# ECU_AutoRC_UC1_r00.net
KiCad netlist of a schematic drawn in Altium Designer
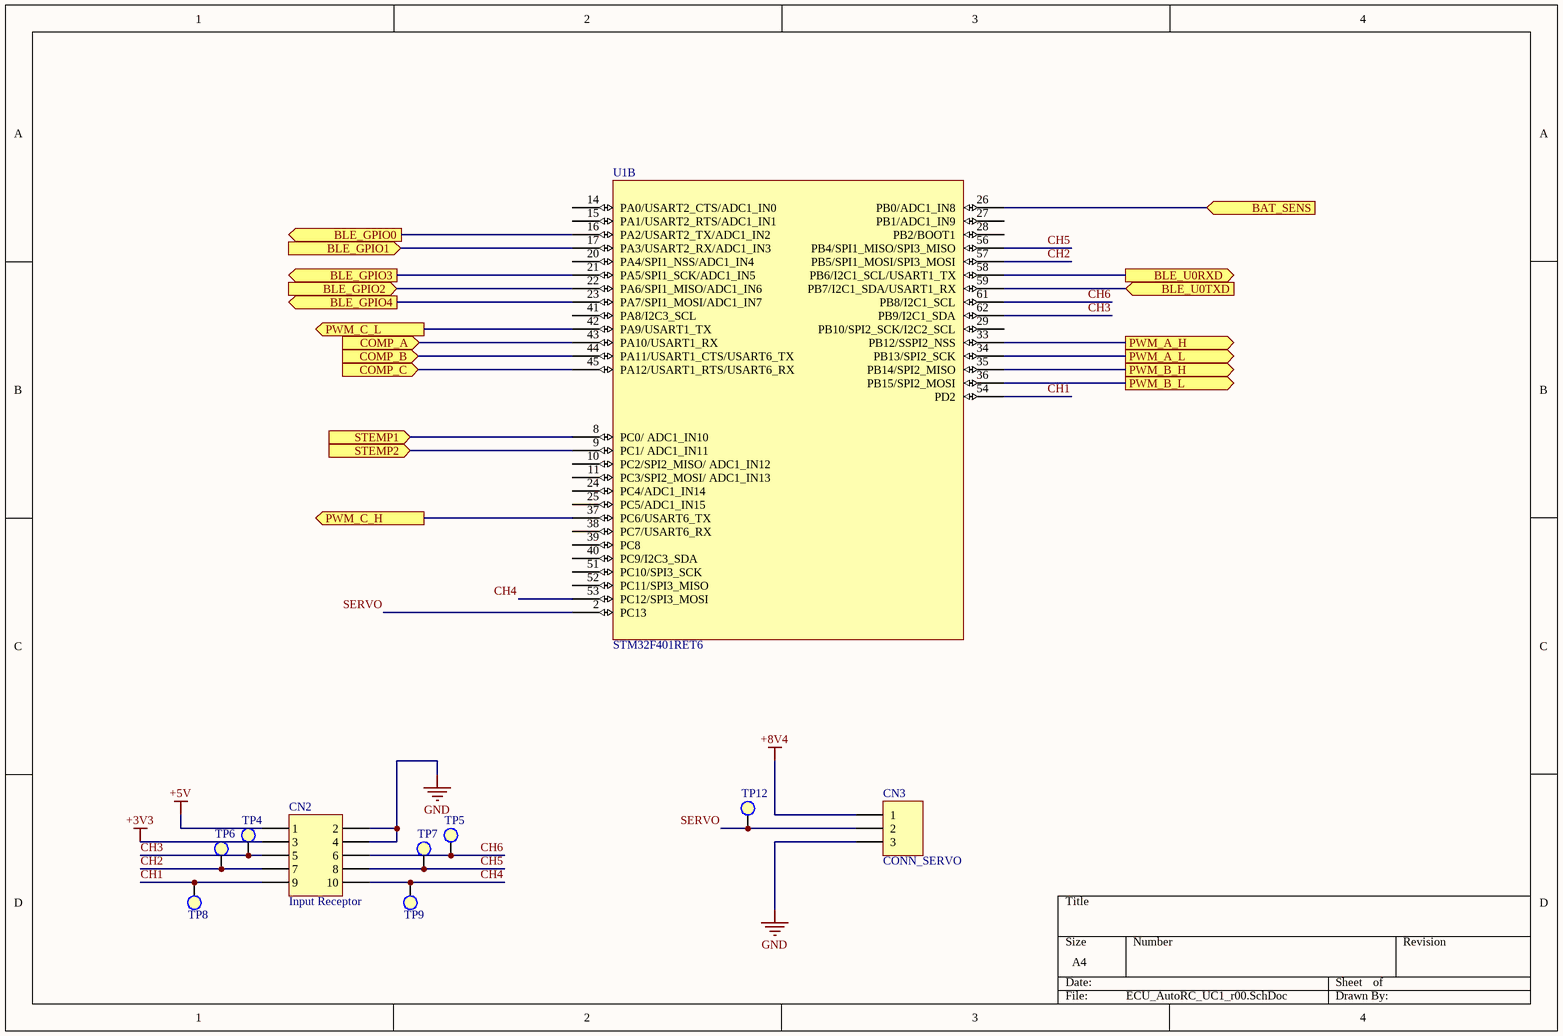
[diagram p0: ECU_AutoRC_UC1_r00.SchDoc]

(export (version "E")
  (design (tool "Eeschema 10.0.6"))
  (components
    (comp (ref "CN2")
      (value "Input Receptor")
      (footprint "HEADER_M_2X5_2.54MM")
      (description "Connector Generic 10 Vias")
      (libsource (lib "ECU_AutoRC_r00") (part "CONN_10P"))
    )
    (comp (ref "CN3")
      (value "CONN_SERVO")
      (footprint "HEADER_M_1X3_2.5MM")
      (description "3 Pin Connector")
      (libsource (lib "ECU_AutoRC_r00") (part "CONN_03P"))
    )
    (comp (ref "TP4")
      (value "Test Point")
      (footprint "TEST_POINT")
      (libsource (lib "ECU_AutoRC_r00") (part "TestPoint"))
    )
    (comp (ref "TP5")
      (value "Test Point")
      (footprint "TEST_POINT")
      (libsource (lib "ECU_AutoRC_r00") (part "TestPoint"))
    )
    (comp (ref "TP6")
      (value "Test Point")
      (footprint "TEST_POINT")
      (libsource (lib "ECU_AutoRC_r00") (part "TestPoint"))
    )
    (comp (ref "TP7")
      (value "Test Point")
      (footprint "TEST_POINT")
      (libsource (lib "ECU_AutoRC_r00") (part "TestPoint"))
    )
    (comp (ref "TP8")
      (value "Test Point")
      (footprint "TEST_POINT")
      (libsource (lib "ECU_AutoRC_r00") (part "TestPoint"))
    )
    (comp (ref "TP9")
      (value "Test Point")
      (footprint "TEST_POINT")
      (libsource (lib "ECU_AutoRC_r00") (part "TestPoint"))
    )
    (comp (ref "TP12")
      (value "Test Point")
      (footprint "TEST_POINT")
      (libsource (lib "ECU_AutoRC_r00") (part "TestPoint"))
    )
    (comp (ref "U1")
      (value "STM32F401RET6")
      (footprint "STM32F401T6")
      (description "STM32 Microcontroller")
      (libsource (lib "ECU_AutoRC_r00") (part "STM32F401RE"))
    )
  )
  (nets
    (net (code "1") (name "+3V3") (class "Default")
      (node (ref "CN2") (pin "3") (pinfunction "3_3") (pintype "passive"))
    )
    (net (code "2") (name "+5V") (class "Default")
      (node (ref "CN2") (pin "1") (pinfunction "1_1") (pintype "passive"))
    )
    (net (code "3") (name "+8V4") (class "Default")
      (node (ref "CN3") (pin "1") (pinfunction "1_1") (pintype "passive"))
    )
    (net (code "4") (name "/BAT_SENS") (class "Default")
      (node (ref "U1") (pin "26") (pinfunction "PB0/ADC1_IN8_26") (pintype "bidirectional"))
    )
    (net (code "5") (name "/BLE_GPIO0") (class "Default")
      (node (ref "U1") (pin "16") (pinfunction "PA2/USART2_TX/ADC1_IN2_16") (pintype "bidirectional"))
    )
    (net (code "6") (name "/BLE_GPIO1") (class "Default")
      (node (ref "U1") (pin "17") (pinfunction "PA3/USART2_RX/ADC1_IN3_17") (pintype "bidirectional"))
    )
    (net (code "7") (name "/BLE_GPIO2") (class "Default")
      (node (ref "U1") (pin "22") (pinfunction "PA6/SPI1_MISO/ADC1_IN6_22") (pintype "bidirectional"))
    )
    (net (code "8") (name "/BLE_GPIO3") (class "Default")
      (node (ref "U1") (pin "21") (pinfunction "PA5/SPI1_SCK/ADC1_IN5_21") (pintype "bidirectional"))
    )
    (net (code "9") (name "/BLE_GPIO4") (class "Default")
      (node (ref "U1") (pin "23") (pinfunction "PA7/SPI1_MOSI/ADC1_IN7_23") (pintype "bidirectional"))
    )
    (net (code "10") (name "/BLE_U0RXD") (class "Default")
      (node (ref "U1") (pin "58") (pinfunction "PB6/I2C1_SCL/USART1_TX_58") (pintype "bidirectional"))
    )
    (net (code "11") (name "/BLE_U0TXD") (class "Default")
      (node (ref "U1") (pin "59") (pinfunction "PB7/I2C1_SDA/USART1_RX_59") (pintype "bidirectional"))
    )
    (net (code "12") (name "/CH1") (class "Default")
      (node (ref "CN2") (pin "9") (pinfunction "9_9") (pintype "passive"))
      (node (ref "TP8") (pin "1") (pintype "passive"))
      (node (ref "U1") (pin "54") (pinfunction "PD2_54") (pintype "bidirectional"))
    )
    (net (code "13") (name "/CH2") (class "Default")
      (node (ref "CN2") (pin "7") (pinfunction "7_7") (pintype "passive"))
      (node (ref "TP6") (pin "1") (pintype "passive"))
      (node (ref "U1") (pin "57") (pinfunction "PB5/SPI1_MOSI/SPI3_MOSI_57") (pintype "bidirectional"))
    )
    (net (code "14") (name "/CH3") (class "Default")
      (node (ref "CN2") (pin "5") (pinfunction "5_5") (pintype "passive"))
      (node (ref "TP4") (pin "1") (pintype "passive"))
      (node (ref "U1") (pin "62") (pinfunction "PB9/I2C1_SDA_62") (pintype "bidirectional"))
    )
    (net (code "15") (name "/CH4") (class "Default")
      (node (ref "CN2") (pin "10") (pinfunction "10_10") (pintype "passive"))
      (node (ref "TP9") (pin "1") (pintype "passive"))
      (node (ref "U1") (pin "53") (pinfunction "PC12/SPI3_MOSI_53") (pintype "bidirectional"))
    )
    (net (code "16") (name "/CH5") (class "Default")
      (node (ref "CN2") (pin "8") (pinfunction "8_8") (pintype "passive"))
      (node (ref "TP7") (pin "1") (pintype "passive"))
      (node (ref "U1") (pin "56") (pinfunction "PB4/SPI1_MISO/SPI3_MISO_56") (pintype "bidirectional"))
    )
    (net (code "17") (name "/CH6") (class "Default")
      (node (ref "CN2") (pin "6") (pinfunction "6_6") (pintype "passive"))
      (node (ref "TP5") (pin "1") (pintype "passive"))
      (node (ref "U1") (pin "61") (pinfunction "PB8/I2C1_SCL_61") (pintype "bidirectional"))
    )
    (net (code "18") (name "/COMP_A") (class "Default")
      (node (ref "U1") (pin "43") (pinfunction "PA10/USART1_RX_43") (pintype "bidirectional"))
    )
    (net (code "19") (name "/COMP_B") (class "Default")
      (node (ref "U1") (pin "44") (pinfunction "PA11/USART1_CTS/USART6_TX_44") (pintype "bidirectional"))
    )
    (net (code "20") (name "/COMP_C") (class "Default")
      (node (ref "U1") (pin "45") (pinfunction "PA12/USART1_RTS/USART6_RX_45") (pintype "bidirectional"))
    )
    (net (code "21") (name "/PWM_A_H") (class "Default")
      (node (ref "U1") (pin "33") (pinfunction "PB12/SSPI2_NSS_33") (pintype "bidirectional"))
    )
    (net (code "22") (name "/PWM_A_L") (class "Default")
      (node (ref "U1") (pin "34") (pinfunction "PB13/SPI2_SCK_34") (pintype "bidirectional"))
    )
    (net (code "23") (name "/PWM_B_H") (class "Default")
      (node (ref "U1") (pin "35") (pinfunction "PB14/SPI2_MISO_35") (pintype "bidirectional"))
    )
    (net (code "24") (name "/PWM_B_L") (class "Default")
      (node (ref "U1") (pin "36") (pinfunction "PB15/SPI2_MOSI_36") (pintype "bidirectional"))
    )
    (net (code "25") (name "/PWM_C_H") (class "Default")
      (node (ref "U1") (pin "37") (pinfunction "PC6/USART6_TX_37") (pintype "bidirectional"))
    )
    (net (code "26") (name "/PWM_C_L") (class "Default")
      (node (ref "U1") (pin "42") (pinfunction "PA9/USART1_TX_42") (pintype "bidirectional"))
    )
    (net (code "27") (name "/SERVO") (class "Default")
      (node (ref "CN3") (pin "2") (pinfunction "2_2") (pintype "passive"))
      (node (ref "TP12") (pin "1") (pintype "passive"))
      (node (ref "U1") (pin "2") (pinfunction "PC13_2") (pintype "bidirectional"))
    )
    (net (code "28") (name "/STEMP1") (class "Default")
      (node (ref "U1") (pin "8") (pinfunction "PC0/_ADC1_IN10_8") (pintype "bidirectional"))
    )
    (net (code "29") (name "/STEMP2") (class "Default")
      (node (ref "U1") (pin "9") (pinfunction "PC1/_ADC1_IN11_9") (pintype "bidirectional"))
    )
    (net (code "30") (name "GND") (class "Default")
      (node (ref "CN2") (pin "2") (pinfunction "2_2") (pintype "passive"))
      (node (ref "CN2") (pin "4") (pinfunction "4_4") (pintype "passive"))
      (node (ref "CN3") (pin "3") (pinfunction "3_3") (pintype "passive"))
    )
    (net (code "31") (name "unconnected-(U1B-PA0{slash}USART2_CTS{slash}ADC1_IN0-Pad14)") (class "Default")
      (node (ref "U1") (pin "14") (pinfunction "PA0/USART2_CTS/ADC1_IN0_14") (pintype "bidirectional"))
    )
    (net (code "32") (name "unconnected-(U1B-PA1{slash}USART2_RTS{slash}ADC1_IN1-Pad15)") (class "Default")
      (node (ref "U1") (pin "15") (pinfunction "PA1/USART2_RTS/ADC1_IN1_15") (pintype "bidirectional"))
    )
    (net (code "33") (name "unconnected-(U1B-PA4{slash}SPI1_NSS{slash}ADC1_IN4-Pad20)") (class "Default")
      (node (ref "U1") (pin "20") (pinfunction "PA4/SPI1_NSS/ADC1_IN4_20") (pintype "bidirectional"))
    )
    (net (code "34") (name "unconnected-(U1B-PA8{slash}I2C3_SCL-Pad41)") (class "Default")
      (node (ref "U1") (pin "41") (pinfunction "PA8/I2C3_SCL_41") (pintype "bidirectional"))
    )
    (net (code "35") (name "unconnected-(U1B-PB1{slash}ADC1_IN9-Pad27)") (class "Default")
      (node (ref "U1") (pin "27") (pinfunction "PB1/ADC1_IN9_27") (pintype "bidirectional"))
    )
    (net (code "36") (name "unconnected-(U1B-PB2{slash}BOOT1-Pad28)") (class "Default")
      (node (ref "U1") (pin "28") (pinfunction "PB2/BOOT1_28") (pintype "bidirectional"))
    )
    (net (code "37") (name "unconnected-(U1B-PB10{slash}SPI2_SCK{slash}I2C2_SCL-Pad29)") (class "Default")
      (node (ref "U1") (pin "29") (pinfunction "PB10/SPI2_SCK/I2C2_SCL_29") (pintype "bidirectional"))
    )
    (net (code "38") (name "unconnected-(U1B-PC2{slash}SPI2_MISO{slash}_ADC1_IN12-Pad10)") (class "Default")
      (node (ref "U1") (pin "10") (pinfunction "PC2/SPI2_MISO/_ADC1_IN12_10") (pintype "bidirectional"))
    )
    (net (code "39") (name "unconnected-(U1B-PC3{slash}SPI2_MOSI{slash}_ADC1_IN13-Pad11)") (class "Default")
      (node (ref "U1") (pin "11") (pinfunction "PC3/SPI2_MOSI/_ADC1_IN13_11") (pintype "bidirectional"))
    )
    (net (code "40") (name "unconnected-(U1B-PC4{slash}ADC1_IN14-Pad24)") (class "Default")
      (node (ref "U1") (pin "24") (pinfunction "PC4/ADC1_IN14_24") (pintype "bidirectional"))
    )
    (net (code "41") (name "unconnected-(U1B-PC5{slash}ADC1_IN15-Pad25)") (class "Default")
      (node (ref "U1") (pin "25") (pinfunction "PC5/ADC1_IN15_25") (pintype "bidirectional"))
    )
    (net (code "42") (name "unconnected-(U1B-PC7{slash}USART6_RX-Pad38)") (class "Default")
      (node (ref "U1") (pin "38") (pinfunction "PC7/USART6_RX_38") (pintype "bidirectional"))
    )
    (net (code "43") (name "unconnected-(U1B-PC8-Pad39)") (class "Default")
      (node (ref "U1") (pin "39") (pinfunction "PC8_39") (pintype "bidirectional"))
    )
    (net (code "44") (name "unconnected-(U1B-PC9{slash}I2C3_SDA-Pad40)") (class "Default")
      (node (ref "U1") (pin "40") (pinfunction "PC9/I2C3_SDA_40") (pintype "bidirectional"))
    )
    (net (code "45") (name "unconnected-(U1B-PC10{slash}SPI3_SCK-Pad51)") (class "Default")
      (node (ref "U1") (pin "51") (pinfunction "PC10/SPI3_SCK_51") (pintype "bidirectional"))
    )
    (net (code "46") (name "unconnected-(U1B-PC11{slash}SPI3_MISO-Pad52)") (class "Default")
      (node (ref "U1") (pin "52") (pinfunction "PC11/SPI3_MISO_52") (pintype "bidirectional"))
    )
  )
)
